# INA220_Current_Sensor_Breakout_REV_A.net
KiCad netlist of a schematic drawn in EAGLE
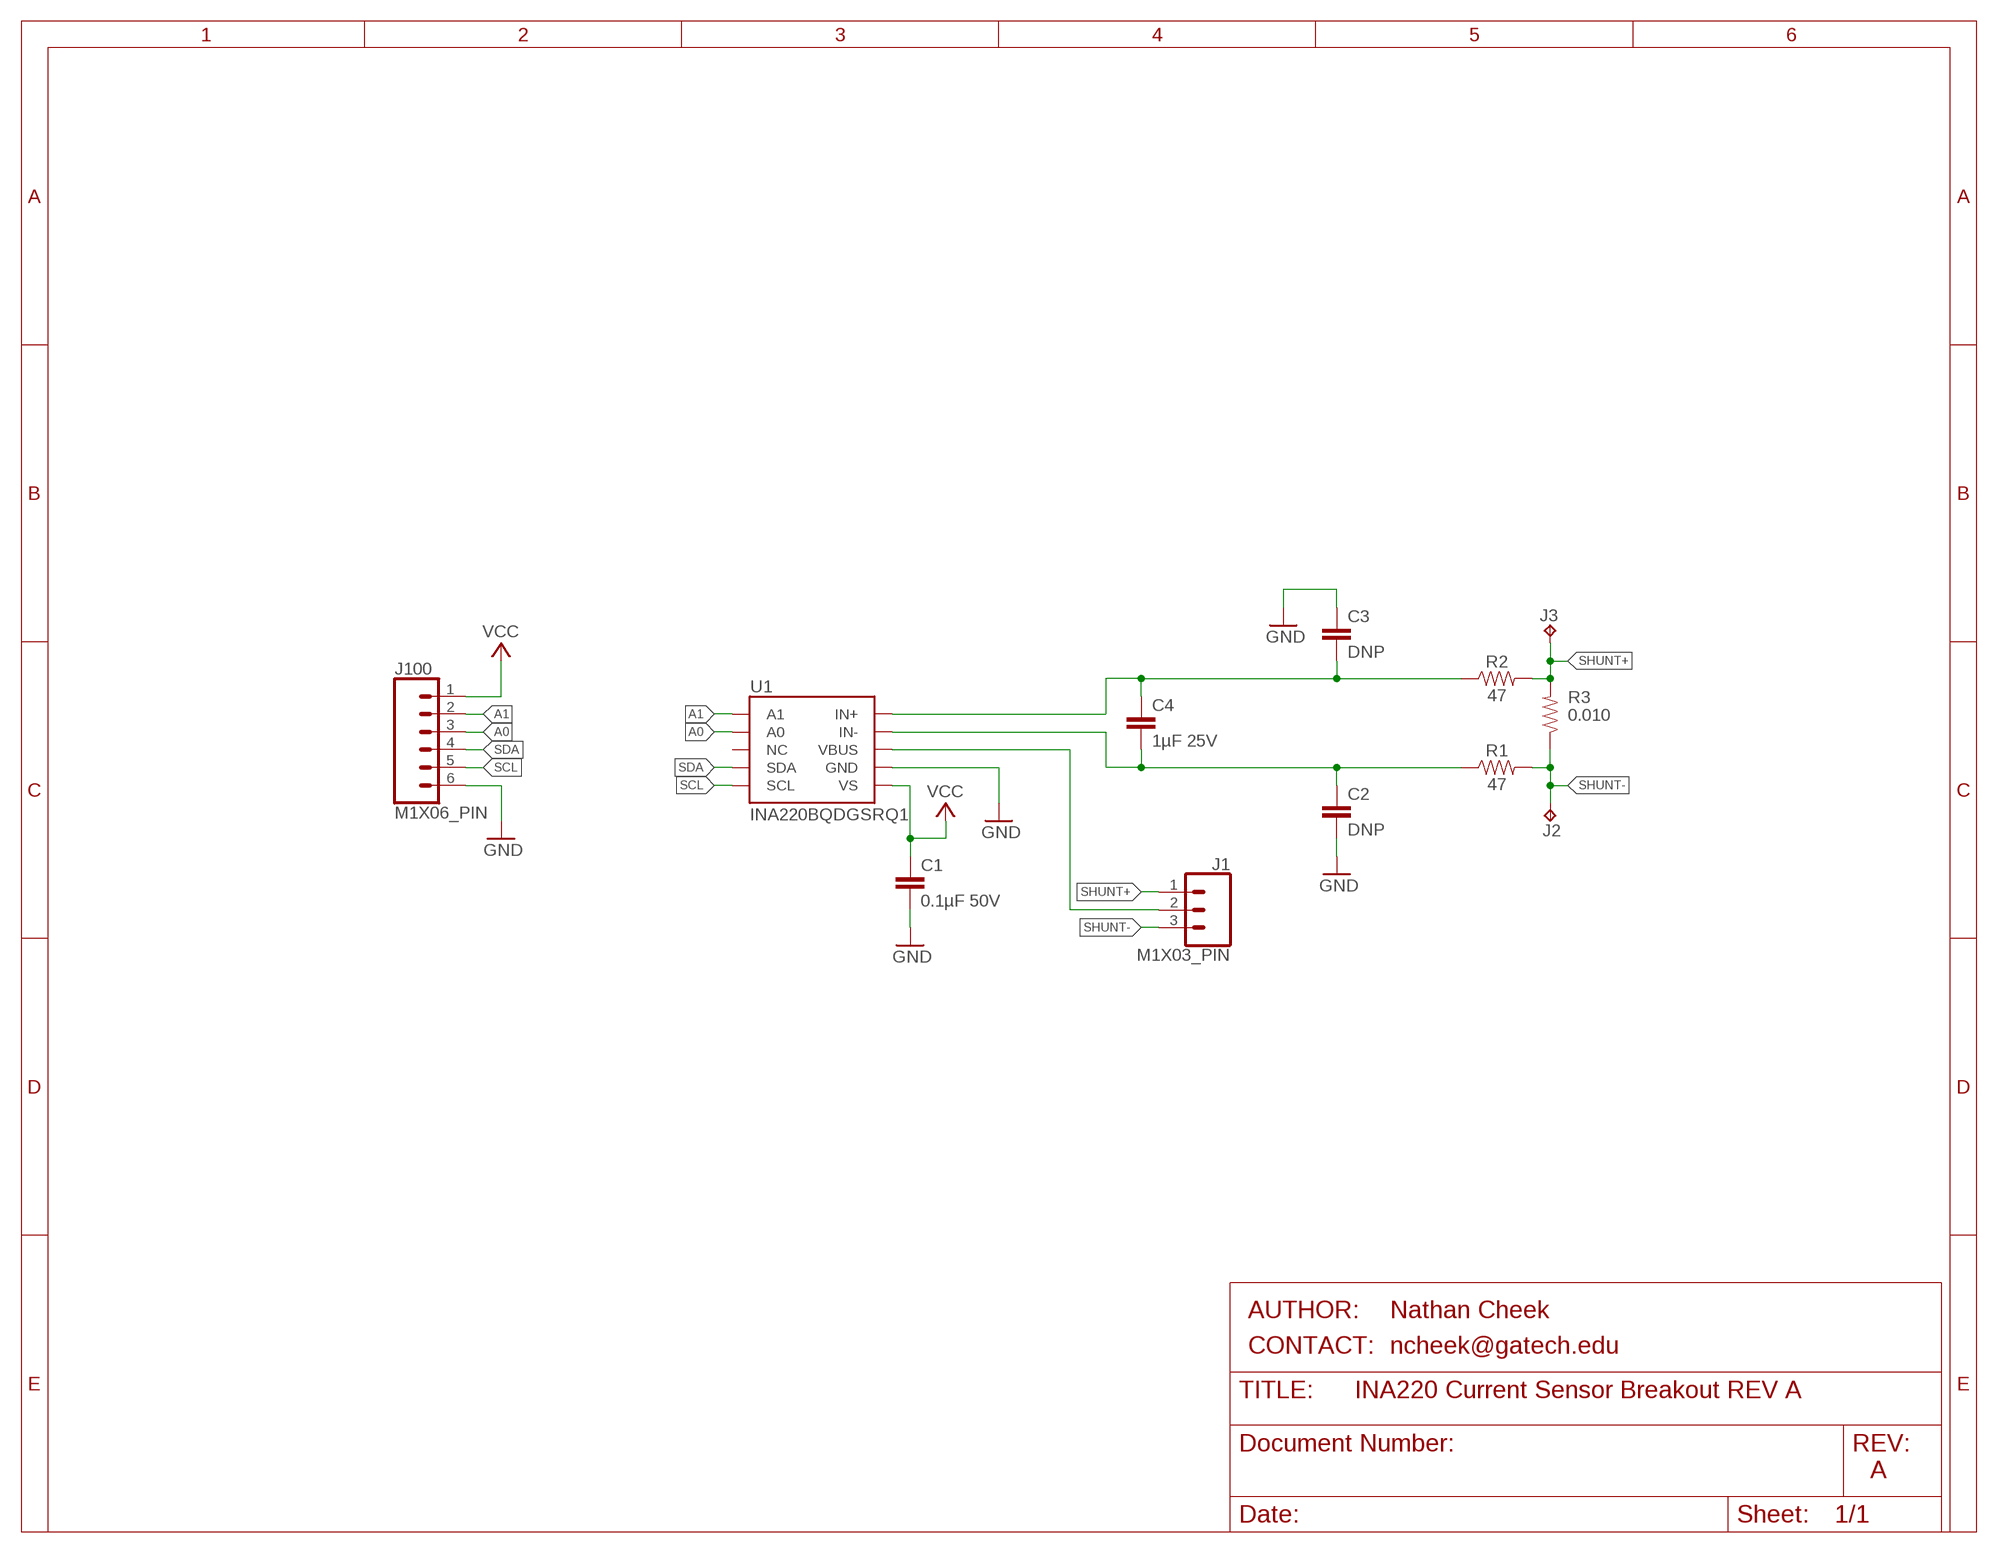
[diagram p0: schematic, sheet 1]

(export (version "E")
  (design (tool "Eeschema 10.0.6"))
  (components
    (comp (ref "C1")
      (value "0.1µF 50V")
      (footprint "eagle-import:C0603")
      (fields
        (field (name "MANUFACTURER") "YAGEO")
        (field (name "MPN") "CC0603KRX7R9BB104")
        (field (name "TOLERANCE") "±10%")
      )
      (libsource (lib "eagle-import") (part "CAPACITOR_YAGEO_CC0603_X7R__50V_±10%0.1UF"))
    )
    (comp (ref "C2")
      (value "DNP")
      (footprint "eagle-import:C0603")
      (libsource (lib "eagle-import") (part "CAPACITOR_YAGEO_CC0603_X7R__50V_±10%DNP"))
    )
    (comp (ref "C3")
      (value "DNP")
      (footprint "eagle-import:C0603")
      (libsource (lib "eagle-import") (part "CAPACITOR_YAGEO_CC0603_X7R__50V_±10%DNP"))
    )
    (comp (ref "C4")
      (value "1µF 25V")
      (footprint "eagle-import:C0603")
      (fields
        (field (name "MANUFACTURER") "YAGEO")
        (field (name "MPN") "CC0603KRX7R8BB105")
        (field (name "TOLERANCE") "±10%")
      )
      (libsource (lib "eagle-import") (part "CAPACITOR_YAGEO_CC0603_X7R__25V_±10%1UF"))
    )
    (comp (ref "J1")
      (value "M1X03_PIN")
      (footprint "eagle-import:1X03")
      (fields (field (name "MANUFACTURER") "Sullins") (field (name "MPN") "PRPC003SAAN-RC"))
      (libsource (lib "eagle-import") (part "M1X03_PIN"))
    )
    (comp (ref "J2")
      (value "BANANA_KEYSTONE_575-4")
      (footprint "eagle-import:575")
      (fields (field (name "MANUFACTURER") "Keystone Electronics") (field (name "MPN") "575-4"))
      (libsource (lib "eagle-import") (part "BANANA_KEYSTONE_575-4"))
    )
    (comp (ref "J3")
      (value "BANANA_KEYSTONE_575-4")
      (footprint "eagle-import:575")
      (fields (field (name "MANUFACTURER") "Keystone Electronics") (field (name "MPN") "575-4"))
      (libsource (lib "eagle-import") (part "BANANA_KEYSTONE_575-4"))
    )
    (comp (ref "J100")
      (value "M1X06_PIN")
      (footprint "eagle-import:1X06")
      (fields (field (name "MANUFACTURER") "Sullins") (field (name "MPN") "PRPC006SAAN-RC"))
      (libsource (lib "eagle-import") (part "M1X06_PIN"))
    )
    (comp (ref "R1")
      (value "47")
      (footprint "eagle-import:R0603")
      (fields
        (field (name "MANUFACTURER") "YAGEO")
        (field (name "MPN") "RC0603FR-0747RL")
        (field (name "TOLERANCE") "±1%")
      )
      (libsource (lib "eagle-import") (part "RESISTOR_YAGEO_RC0603FR_47"))
    )
    (comp (ref "R2")
      (value "47")
      (footprint "eagle-import:R0603")
      (fields
        (field (name "MANUFACTURER") "YAGEO")
        (field (name "MPN") "RC0603FR-0747RL")
        (field (name "TOLERANCE") "±1%")
      )
      (libsource (lib "eagle-import") (part "RESISTOR_YAGEO_RC0603FR_47"))
    )
    (comp (ref "R3")
      (value "0.010")
      (footprint "eagle-import:R0805")
      (fields
        (field (name "MANUFACTURER") "Panasonic")
        (field (name "MPN") "ERJ-6CWDR010V")
        (field (name "TOLERANCE") "±0.5%")
      )
      (libsource (lib "eagle-import") (part "RESISTOR_PANASONIC_ERJ-6CWD_0.01"))
    )
    (comp (ref "U1")
      (value "INA220BQDGSRQ1")
      (footprint "eagle-import:VSSOP-10")
      (fields (field (name "MANUFACTURER") "Texas Instruments"))
      (libsource (lib "eagle-import") (part "INA220BQDGSRQ1"))
    )
  )
  (nets
    (net (code "1") (name "A0") (class "Default")
      (node (ref "J100") (pin "3") (pinfunction "3_3") (pintype "passive"))
      (node (ref "U1") (pin "P$2") (pinfunction "A0_P$2") (pintype "bidirectional"))
    )
    (net (code "2") (name "A1") (class "Default")
      (node (ref "J100") (pin "2") (pinfunction "2_2") (pintype "passive"))
      (node (ref "U1") (pin "P$1") (pinfunction "A1_P$1") (pintype "bidirectional"))
    )
    (net (code "3") (name "GND") (class "Default")
      (node (ref "C1") (pin "2") (pinfunction "2_2") (pintype "passive"))
      (node (ref "C2") (pin "1") (pinfunction "1_1") (pintype "passive"))
      (node (ref "C3") (pin "2") (pinfunction "2_2") (pintype "passive"))
      (node (ref "J100") (pin "6") (pinfunction "6_6") (pintype "passive"))
      (node (ref "U1") (pin "P$7") (pinfunction "GND_P$7") (pintype "bidirectional"))
    )
    (net (code "4") (name "Net-(U1-IN+)") (class "Default")
      (node (ref "C3") (pin "1") (pinfunction "1_1") (pintype "passive"))
      (node (ref "C4") (pin "2") (pinfunction "2_2") (pintype "passive"))
      (node (ref "R2") (pin "1") (pinfunction "1_1") (pintype "passive"))
      (node (ref "U1") (pin "P$10") (pinfunction "IN+_P$10") (pintype "bidirectional"))
    )
    (net (code "5") (name "Net-(U1-IN-)") (class "Default")
      (node (ref "C2") (pin "2") (pinfunction "2_2") (pintype "passive"))
      (node (ref "C4") (pin "1") (pinfunction "1_1") (pintype "passive"))
      (node (ref "R1") (pin "1") (pinfunction "1_1") (pintype "passive"))
      (node (ref "U1") (pin "P$9") (pinfunction "IN-_P$9") (pintype "bidirectional"))
    )
    (net (code "6") (name "Net-(U1-VBUS)") (class "Default")
      (node (ref "J1") (pin "2") (pinfunction "2_2") (pintype "passive"))
      (node (ref "U1") (pin "P$8") (pinfunction "VBUS_P$8") (pintype "bidirectional"))
    )
    (net (code "7") (name "SCL") (class "Default")
      (node (ref "J100") (pin "5") (pinfunction "5_5") (pintype "passive"))
      (node (ref "U1") (pin "P$5") (pinfunction "SCL_P$5") (pintype "bidirectional"))
    )
    (net (code "8") (name "SDA") (class "Default")
      (node (ref "J100") (pin "4") (pinfunction "4_4") (pintype "passive"))
      (node (ref "U1") (pin "P$4") (pinfunction "SDA_P$4") (pintype "bidirectional"))
    )
    (net (code "9") (name "SHUNT+") (class "Default")
      (node (ref "J1") (pin "1") (pinfunction "1_1") (pintype "passive"))
      (node (ref "J3") (pin "P$1") (pinfunction "1_P$1") (pintype "passive"))
      (node (ref "R2") (pin "2") (pinfunction "2_2") (pintype "passive"))
      (node (ref "R3") (pin "2") (pinfunction "2_2") (pintype "passive"))
    )
    (net (code "10") (name "SHUNT-") (class "Default")
      (node (ref "J1") (pin "3") (pinfunction "3_3") (pintype "passive"))
      (node (ref "J2") (pin "P$1") (pinfunction "1_P$1") (pintype "passive"))
      (node (ref "R1") (pin "2") (pinfunction "2_2") (pintype "passive"))
      (node (ref "R3") (pin "1") (pinfunction "1_1") (pintype "passive"))
    )
    (net (code "11") (name "VCC") (class "Default")
      (node (ref "C1") (pin "1") (pinfunction "1_1") (pintype "passive"))
      (node (ref "J100") (pin "1") (pinfunction "1_1") (pintype "passive"))
      (node (ref "U1") (pin "P$6") (pinfunction "VS_P$6") (pintype "bidirectional"))
    )
    (net (code "12") (name "unconnected-(U1-NC-PadP$3)") (class "Default")
      (node (ref "U1") (pin "P$3") (pinfunction "NC_P$3") (pintype "bidirectional"))
    )
  )
)
